# Controlador_repetidora.net
KiCad netlist of a schematic drawn in EAGLE
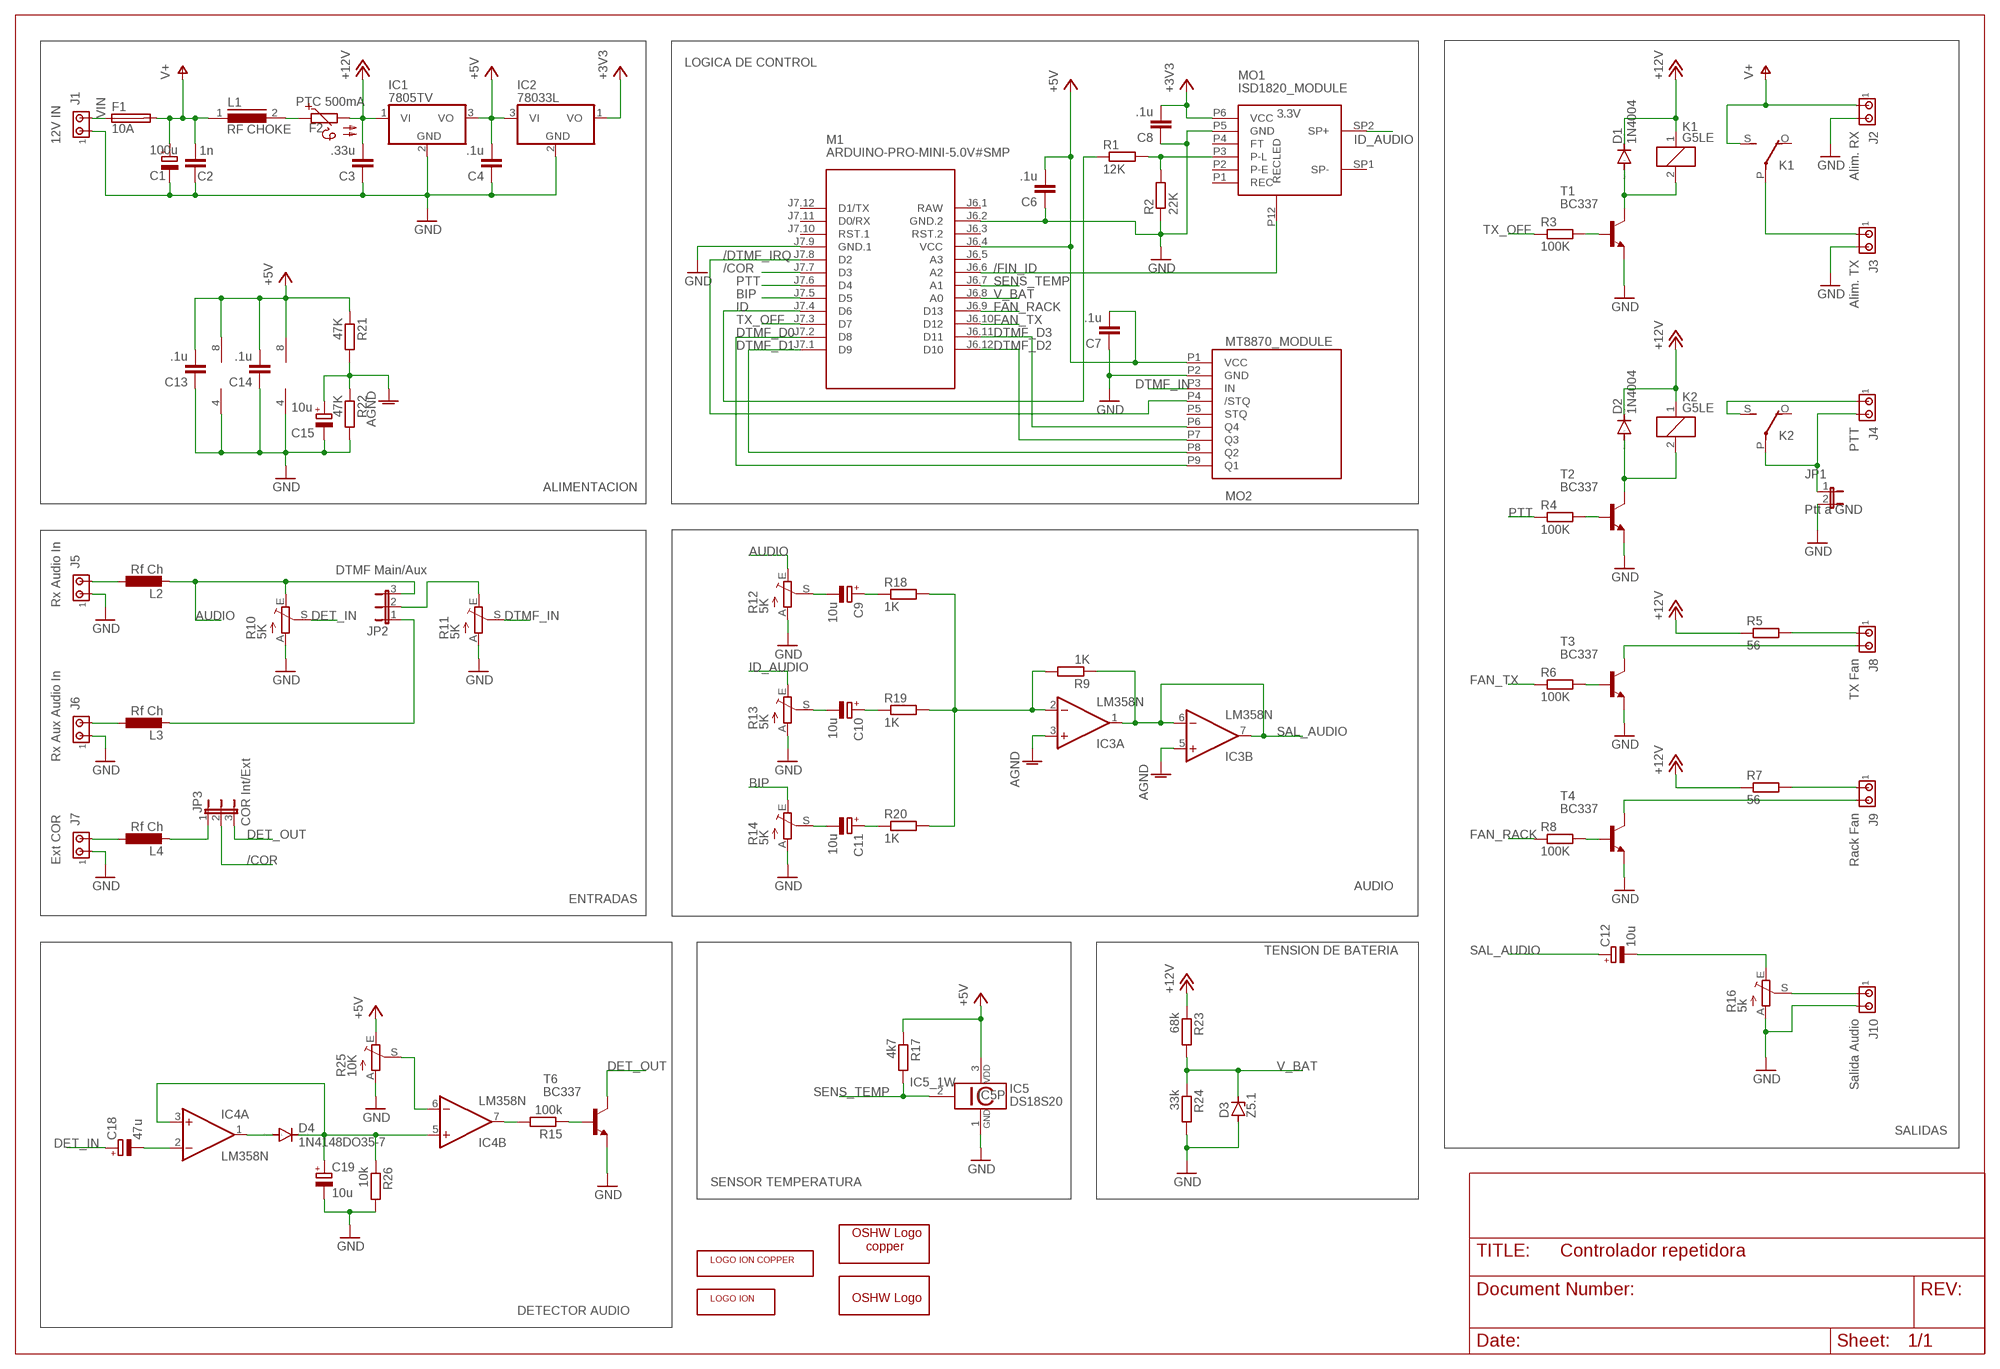
[diagram p0: schematic, sheet 1]

(export (version "E")
  (design (tool "Eeschema 10.0.6"))
  (components
    (comp (ref "C1")
      (value "100u")
      (footprint "eagle-import:E2,5-7")
      (libsource (lib "eagle-import") (part "CPOL-EUE2.5-7"))
    )
    (comp (ref "C2")
      (value "1n")
      (footprint "eagle-import:C025-025X050")
      (libsource (lib "eagle-import") (part "C-EU025-025X050"))
    )
    (comp (ref "C3")
      (value ".33u")
      (footprint "eagle-import:C025-025X050")
      (libsource (lib "eagle-import") (part "C-EU025-025X050"))
    )
    (comp (ref "C4")
      (value ".1u")
      (footprint "eagle-import:C025-025X050")
      (libsource (lib "eagle-import") (part "C-EU025-025X050"))
    )
    (comp (ref "C6")
      (value ".1u")
      (footprint "eagle-import:C025-025X050")
      (libsource (lib "eagle-import") (part "C-EU025-025X050"))
    )
    (comp (ref "C7")
      (value ".1u")
      (footprint "eagle-import:C025-025X050")
      (libsource (lib "eagle-import") (part "C-EU025-025X050"))
    )
    (comp (ref "C8")
      (value ".1u")
      (footprint "eagle-import:C025-025X050")
      (libsource (lib "eagle-import") (part "C-EU025-025X050"))
    )
    (comp (ref "C9")
      (value "10u")
      (footprint "eagle-import:E1,8-4")
      (libsource (lib "eagle-import") (part "CPOL-EUE1.8-4"))
    )
    (comp (ref "C10")
      (value "10u")
      (footprint "eagle-import:E1,8-4")
      (libsource (lib "eagle-import") (part "CPOL-EUE1.8-4"))
    )
    (comp (ref "C11")
      (value "10u")
      (footprint "eagle-import:E1,8-4")
      (libsource (lib "eagle-import") (part "CPOL-EUE1.8-4"))
    )
    (comp (ref "C12")
      (value "10u")
      (footprint "eagle-import:E1,8-4")
      (libsource (lib "eagle-import") (part "CPOL-EUE1.8-4"))
    )
    (comp (ref "C13")
      (value ".1u")
      (footprint "eagle-import:C025-025X050")
      (libsource (lib "eagle-import") (part "C-EU025-025X050"))
    )
    (comp (ref "C14")
      (value ".1u")
      (footprint "eagle-import:C025-025X050")
      (libsource (lib "eagle-import") (part "C-EU025-025X050"))
    )
    (comp (ref "C15")
      (value "10u")
      (footprint "eagle-import:E1,8-4")
      (libsource (lib "eagle-import") (part "CPOL-EUE1.8-4"))
    )
    (comp (ref "C18")
      (value "47u")
      (footprint "eagle-import:E1,8-4")
      (libsource (lib "eagle-import") (part "CPOL-EUE1.8-4"))
    )
    (comp (ref "C19")
      (value "10u")
      (footprint "eagle-import:E1,8-4")
      (libsource (lib "eagle-import") (part "CPOL-EUE1.8-4"))
    )
    (comp (ref "D1")
      (value "1N4004")
      (footprint "eagle-import:DO41-10")
      (libsource (lib "eagle-import") (part "1N4004"))
    )
    (comp (ref "D2")
      (value "1N4004")
      (footprint "eagle-import:DO41-10")
      (libsource (lib "eagle-import") (part "1N4004"))
    )
    (comp (ref "D3")
      (value "Z5.1")
      (footprint "eagle-import:DO34Z7")
      (libsource (lib "eagle-import") (part "ZENER-DIODEDO34-7"))
    )
    (comp (ref "D4")
      (value "1N4148DO35-7")
      (footprint "eagle-import:DO35-7")
      (libsource (lib "eagle-import") (part "1N4148DO35-7"))
    )
    (comp (ref "F1")
      (value "10A")
      (footprint "eagle-import:19559")
      (fields (field (name "MPN") "55900000001"))
      (libsource (lib "eagle-import") (part "19559"))
    )
    (comp (ref "F2")
      (value "PTC 500mA")
      (footprint "eagle-import:P660A")
      (libsource (lib "eagle-import") (part "PTC660A"))
    )
    (comp (ref "GOLD_ORB_SM1")
      (value "OSHWLOGOLOGO8MM")
      (footprint "eagle-import:OSHW_8MM")
      (libsource (lib "eagle-import") (part "OSHWLOGOLOGO8MM"))
    )
    (comp (ref "GOLD_ORB_SM2")
      (value "OSHWLOGO_COPPER8MM_COPPER")
      (footprint "eagle-import:OSHW_8MM_COPPER")
      (libsource (lib "eagle-import") (part "OSHWLOGO_COPPER8MM_COPPER"))
    )
    (comp (ref "IC1")
      (value "7805TV")
      (footprint "eagle-import:TO220V")
      (libsource (lib "eagle-import") (part "78TV05"))
    )
    (comp (ref "IC2")
      (value "78033L")
      (footprint "eagle-import:TO92")
      (libsource (lib "eagle-import") (part "78033L"))
    )
    (comp (ref "IC3")
      (value "LM358N")
      (footprint "eagle-import:DIL08")
      (libsource (lib "eagle-import") (part "LM358N"))
    )
    (comp (ref "IC4")
      (value "LM358N")
      (footprint "eagle-import:DIL08")
      (libsource (lib "eagle-import") (part "LM358N"))
    )
    (comp (ref "IC5")
      (value "DS18S20")
      (footprint "eagle-import:TO92-")
      (libsource (lib "eagle-import") (part "DS18S20"))
    )
    (comp (ref "J1")
      (value "12V IN")
      (footprint "eagle-import:1X2MTA")
      (libsource (lib "eagle-import") (part "MTA02-156"))
    )
    (comp (ref "J2")
      (value "Alim. RX")
      (footprint "eagle-import:1X2MTA")
      (libsource (lib "eagle-import") (part "MTA02-156"))
    )
    (comp (ref "J3")
      (value "Alim. TX")
      (footprint "eagle-import:1X2MTA")
      (libsource (lib "eagle-import") (part "MTA02-156"))
    )
    (comp (ref "J4")
      (value "PTT")
      (footprint "eagle-import:10X02MTA")
      (libsource (lib "eagle-import") (part "MTA02-100"))
    )
    (comp (ref "J5")
      (value "Rx Audio In")
      (footprint "eagle-import:10X02MTA")
      (libsource (lib "eagle-import") (part "MTA02-100"))
    )
    (comp (ref "J6")
      (value "Rx Aux Audio In")
      (footprint "eagle-import:10X02MTA")
      (libsource (lib "eagle-import") (part "MTA02-100"))
    )
    (comp (ref "J7")
      (value "Ext COR")
      (footprint "eagle-import:10X02MTA")
      (libsource (lib "eagle-import") (part "MTA02-100"))
    )
    (comp (ref "J8")
      (value "TX Fan")
      (footprint "eagle-import:10X02MTA")
      (libsource (lib "eagle-import") (part "MTA02-100"))
    )
    (comp (ref "J9")
      (value "Rack Fan")
      (footprint "eagle-import:10X02MTA")
      (libsource (lib "eagle-import") (part "MTA02-100"))
    )
    (comp (ref "J10")
      (value "Salida Audio")
      (footprint "eagle-import:10X02MTA")
      (libsource (lib "eagle-import") (part "MTA02-100"))
    )
    (comp (ref "JP1")
      (value "Ptt a GND")
      (footprint "eagle-import:JP1")
      (libsource (lib "eagle-import") (part "JP1E"))
    )
    (comp (ref "JP2")
      (value "DTMF Main/Aux")
      (footprint "eagle-import:JP2")
      (libsource (lib "eagle-import") (part "JP2E"))
    )
    (comp (ref "JP3")
      (value "COR Int/Ext")
      (footprint "eagle-import:JP2")
      (libsource (lib "eagle-import") (part "JP2E"))
    )
    (comp (ref "K1")
      (value "G5LE")
      (footprint "eagle-import:G5LE")
      (libsource (lib "eagle-import") (part "G5LE"))
    )
    (comp (ref "K2")
      (value "G5LE")
      (footprint "eagle-import:G5LE")
      (libsource (lib "eagle-import") (part "G5LE"))
    )
    (comp (ref "L1")
      (value "RF CHOKE")
      (footprint "eagle-import:82114A")
      (libsource (lib "eagle-import") (part "82114A"))
    )
    (comp (ref "L2")
      (value "Rf Ch")
      (footprint "eagle-import:0207_10")
      (libsource (lib "eagle-import") (part "L-EU0207/10"))
    )
    (comp (ref "L3")
      (value "Rf Ch")
      (footprint "eagle-import:0207_2V")
      (libsource (lib "eagle-import") (part "L-EU0207/2V"))
    )
    (comp (ref "L4")
      (value "Rf Ch")
      (footprint "eagle-import:0207_2V")
      (libsource (lib "eagle-import") (part "L-EU0207/2V"))
    )
    (comp (ref "M1")
      (value "ARDUINO-PRO-MINI-5.0V#SMP")
      (footprint "eagle-import:ARDUINO-PRO-MINI#SMP")
      (libsource (lib "eagle-import") (part "ARDUINO-PRO-MINI-#SMP5.0V"))
    )
    (comp (ref "MO1")
      (value "ISD1820_MODULE")
      (footprint "eagle-import:ISD1820_MODULE")
      (libsource (lib "eagle-import") (part "ISD1820_MODULE"))
    )
    (comp (ref "MO2")
      (value "MT8870_MODULE")
      (footprint "eagle-import:MT8870_MODULE")
      (libsource (lib "eagle-import") (part "MT8870_MODULE"))
    )
    (comp (ref "R1")
      (value "12K")
      (footprint "eagle-import:0207_12")
      (libsource (lib "eagle-import") (part "R-EU_0207/12"))
    )
    (comp (ref "R2")
      (value "22K")
      (footprint "eagle-import:0204_7")
      (libsource (lib "eagle-import") (part "R-EU_0204/7"))
    )
    (comp (ref "R3")
      (value "100K")
      (footprint "eagle-import:0207_10")
      (libsource (lib "eagle-import") (part "R-EU_0207/10"))
    )
    (comp (ref "R4")
      (value "100K")
      (footprint "eagle-import:0207_15")
      (libsource (lib "eagle-import") (part "R-EU_0207/15"))
    )
    (comp (ref "R5")
      (value "56")
      (footprint "eagle-import:0204_7")
      (libsource (lib "eagle-import") (part "R-EU_0204/7"))
    )
    (comp (ref "R6")
      (value "100K")
      (footprint "eagle-import:0207_2V")
      (libsource (lib "eagle-import") (part "R-EU_0207/2V"))
    )
    (comp (ref "R7")
      (value "56")
      (footprint "eagle-import:0204_7")
      (libsource (lib "eagle-import") (part "R-EU_0204/7"))
    )
    (comp (ref "R8")
      (value "100K")
      (footprint "eagle-import:0207_2V")
      (libsource (lib "eagle-import") (part "R-EU_0207/2V"))
    )
    (comp (ref "R9")
      (value "1K")
      (footprint "eagle-import:0204_7")
      (libsource (lib "eagle-import") (part "R-EU_0204/7"))
    )
    (comp (ref "R10")
      (value "5K")
      (footprint "eagle-import:CA6H")
      (libsource (lib "eagle-import") (part "TRIM_EU-CA6H"))
    )
    (comp (ref "R11")
      (value "5K")
      (footprint "eagle-import:CA6H")
      (libsource (lib "eagle-import") (part "TRIM_EU-CA6H"))
    )
    (comp (ref "R12")
      (value "5K")
      (footprint "eagle-import:CA6H")
      (libsource (lib "eagle-import") (part "TRIM_EU-CA6H"))
    )
    (comp (ref "R13")
      (value "5K")
      (footprint "eagle-import:CA6H")
      (libsource (lib "eagle-import") (part "TRIM_EU-CA6H"))
    )
    (comp (ref "R14")
      (value "5K")
      (footprint "eagle-import:CA6H")
      (libsource (lib "eagle-import") (part "TRIM_EU-CA6H"))
    )
    (comp (ref "R15")
      (value "100k")
      (footprint "eagle-import:0204_5")
      (libsource (lib "eagle-import") (part "R-EU_0204/5"))
    )
    (comp (ref "R16")
      (value "5k")
      (footprint "eagle-import:CA6H")
      (libsource (lib "eagle-import") (part "TRIM_EU-CA6H"))
    )
    (comp (ref "R17")
      (value "4k7")
      (footprint "eagle-import:0204_7")
      (libsource (lib "eagle-import") (part "R-EU_0204/7"))
    )
    (comp (ref "R18")
      (value "1K")
      (footprint "eagle-import:0204_7")
      (libsource (lib "eagle-import") (part "R-EU_0204/7"))
    )
    (comp (ref "R19")
      (value "1K")
      (footprint "eagle-import:0207_5V")
      (libsource (lib "eagle-import") (part "R-EU_0207/5V"))
    )
    (comp (ref "R20")
      (value "1K")
      (footprint "eagle-import:0204_7")
      (libsource (lib "eagle-import") (part "R-EU_0204/7"))
    )
    (comp (ref "R21")
      (value "47K")
      (footprint "eagle-import:0204_7")
      (libsource (lib "eagle-import") (part "R-EU_0204/7"))
    )
    (comp (ref "R22")
      (value "47K")
      (footprint "eagle-import:0207_2V")
      (libsource (lib "eagle-import") (part "R-EU_0207/2V"))
    )
    (comp (ref "R23")
      (value "68k")
      (footprint "eagle-import:0207_12")
      (libsource (lib "eagle-import") (part "R-EU_0207/12"))
    )
    (comp (ref "R24")
      (value "33k")
      (footprint "eagle-import:0204_7")
      (libsource (lib "eagle-import") (part "R-EU_0204/7"))
    )
    (comp (ref "R25")
      (value "10K")
      (footprint "eagle-import:CA6V")
      (libsource (lib "eagle-import") (part "TRIM_EU-CA6V"))
    )
    (comp (ref "R26")
      (value "10k")
      (footprint "eagle-import:0204_7")
      (libsource (lib "eagle-import") (part "R-EU_0204/7"))
    )
    (comp (ref "T1")
      (value "BC337")
      (footprint "eagle-import:TO92")
      (libsource (lib "eagle-import") (part "BC337"))
    )
    (comp (ref "T2")
      (value "BC337")
      (footprint "eagle-import:TO92")
      (libsource (lib "eagle-import") (part "BC337"))
    )
    (comp (ref "T3")
      (value "BC337")
      (footprint "eagle-import:TO92")
      (libsource (lib "eagle-import") (part "BC337"))
    )
    (comp (ref "T4")
      (value "BC337")
      (footprint "eagle-import:TO92")
      (libsource (lib "eagle-import") (part "BC337"))
    )
    (comp (ref "T6")
      (value "BC337")
      (footprint "eagle-import:TO92")
      (libsource (lib "eagle-import") (part "BC337"))
    )
    (comp (ref "U$1")
      (value "LOGO_ION")
      (footprint "eagle-import:LOGO_ION_SILK")
      (libsource (lib "eagle-import") (part "LOGO_ION"))
    )
    (comp (ref "U$2")
      (value "LOGO_ION_COOPER")
      (footprint "eagle-import:LOGO_ION_COPPER")
      (libsource (lib "eagle-import") (part "LOGO_ION_COOPER"))
    )
  )
  (nets
    (net (code "1") (name "+3V3") (class "Default")
      (node (ref "C8") (pin "2") (pinfunction "2_2") (pintype "passive"))
      (node (ref "IC2") (pin "1") (pinfunction "VO_1") (pintype "passive"))
      (node (ref "MO1") (pin "P6") (pinfunction "VCC_P6") (pintype "power_in"))
    )
    (net (code "2") (name "+5V") (class "Default")
      (node (ref "C13") (pin "2") (pinfunction "2_2") (pintype "passive"))
      (node (ref "C14") (pin "2") (pinfunction "2_2") (pintype "passive"))
      (node (ref "C4") (pin "2") (pinfunction "2_2") (pintype "passive"))
      (node (ref "C6") (pin "2") (pinfunction "2_2") (pintype "passive"))
      (node (ref "C7") (pin "2") (pinfunction "2_2") (pintype "passive"))
      (node (ref "IC1") (pin "3") (pinfunction "VO_3") (pintype "passive"))
      (node (ref "IC2") (pin "3") (pinfunction "VI_3") (pintype "input"))
      (node (ref "IC3") (pin "8") (pinfunction "V+_8") (pintype "power_in"))
      (node (ref "IC4") (pin "8") (pinfunction "V+_8") (pintype "power_in"))
      (node (ref "IC5") (pin "3") (pinfunction "VDD_3") (pintype "power_in"))
      (node (ref "M1") (pin "J6.4") (pinfunction "VCC_J6.4") (pintype "power_in"))
      (node (ref "MO2") (pin "P1") (pinfunction "VCC_P1") (pintype "power_in"))
      (node (ref "R17") (pin "1") (pinfunction "1_1") (pintype "passive"))
      (node (ref "R21") (pin "1") (pinfunction "1_1") (pintype "passive"))
      (node (ref "R25") (pin "E") (pinfunction "E_E") (pintype "passive"))
    )
    (net (code "3") (name "+12V") (class "Default")
      (node (ref "C3") (pin "2") (pinfunction "2_2") (pintype "passive"))
      (node (ref "D1") (pin "C") (pinfunction "C_C") (pintype "passive"))
      (node (ref "D2") (pin "C") (pinfunction "C_C") (pintype "passive"))
      (node (ref "F2") (pin "2") (pinfunction "2_2") (pintype "passive"))
      (node (ref "IC1") (pin "1") (pinfunction "VI_1") (pintype "input"))
      (node (ref "K1") (pin "1") (pinfunction "1_1") (pintype "passive"))
      (node (ref "K2") (pin "1") (pinfunction "1_1") (pintype "passive"))
      (node (ref "R23") (pin "1") (pinfunction "1_1") (pintype "passive"))
      (node (ref "R5") (pin "1") (pinfunction "1_1") (pintype "passive"))
      (node (ref "R7") (pin "1") (pinfunction "1_1") (pintype "passive"))
    )
    (net (code "4") (name "/AUDIO") (class "Default")
      (node (ref "JP2") (pin "3") (pinfunction "3_3") (pintype "passive"))
      (node (ref "L2") (pin "2") (pinfunction "2_2") (pintype "passive"))
      (node (ref "R10") (pin "E") (pinfunction "E_E") (pintype "passive"))
      (node (ref "R12") (pin "E") (pinfunction "E_E") (pintype "passive"))
    )
    (net (code "5") (name "/BIP") (class "Default")
      (node (ref "M1") (pin "J7.5") (pinfunction "D5_J7.5") (pintype "bidirectional"))
      (node (ref "R14") (pin "E") (pinfunction "E_E") (pintype "passive"))
    )
    (net (code "6") (name "/DET_IN") (class "Default")
      (node (ref "C18") (pin "+") (pinfunction "+_+") (pintype "passive"))
      (node (ref "R10") (pin "S") (pinfunction "S_S") (pintype "passive"))
    )
    (net (code "7") (name "/DET_OUT") (class "Default")
      (node (ref "JP3") (pin "3") (pinfunction "3_3") (pintype "passive"))
      (node (ref "T6") (pin "3") (pinfunction "C_3") (pintype "passive"))
    )
    (net (code "8") (name "/DTMF_D0") (class "Default")
      (node (ref "M1") (pin "J7.2") (pinfunction "D8_J7.2") (pintype "bidirectional"))
      (node (ref "MO2") (pin "P9") (pinfunction "Q1_P9") (pintype "output"))
    )
    (net (code "9") (name "/DTMF_D1") (class "Default")
      (node (ref "M1") (pin "J7.1") (pinfunction "D9_J7.1") (pintype "bidirectional"))
      (node (ref "MO2") (pin "P8") (pinfunction "Q2_P8") (pintype "output"))
    )
    (net (code "10") (name "/DTMF_D2") (class "Default")
      (node (ref "M1") (pin "J6.12") (pinfunction "D10_J6.12") (pintype "bidirectional"))
      (node (ref "MO2") (pin "P7") (pinfunction "Q3_P7") (pintype "output"))
    )
    (net (code "11") (name "/DTMF_D3") (class "Default")
      (node (ref "M1") (pin "J6.11") (pinfunction "D11_J6.11") (pintype "bidirectional"))
      (node (ref "MO2") (pin "P6") (pinfunction "Q4_P6") (pintype "output"))
    )
    (net (code "12") (name "/DTMF_IN") (class "Default")
      (node (ref "MO2") (pin "P3") (pinfunction "IN_P3") (pintype "input"))
      (node (ref "R11") (pin "S") (pinfunction "S_S") (pintype "passive"))
    )
    (net (code "13") (name "/FAN_RACK") (class "Default")
      (node (ref "M1") (pin "J6.9") (pinfunction "D13_J6.9") (pintype "bidirectional"))
      (node (ref "R8") (pin "1") (pinfunction "1_1") (pintype "passive"))
    )
    (net (code "14") (name "/FAN_TX") (class "Default")
      (node (ref "M1") (pin "J6.10") (pinfunction "D12_J6.10") (pintype "bidirectional"))
      (node (ref "R6") (pin "1") (pinfunction "1_1") (pintype "passive"))
    )
    (net (code "15") (name "/ID") (class "Default")
      (node (ref "M1") (pin "J7.4") (pinfunction "D6_J7.4") (pintype "bidirectional"))
      (node (ref "R1") (pin "1") (pinfunction "1_1") (pintype "passive"))
    )
    (net (code "16") (name "/ID_AUDIO") (class "Default")
      (node (ref "MO1") (pin "SP2") (pinfunction "SP+_SP2") (pintype "output"))
      (node (ref "R13") (pin "E") (pinfunction "E_E") (pintype "passive"))
    )
    (net (code "17") (name "/PTT") (class "Default")
      (node (ref "M1") (pin "J7.6") (pinfunction "D4_J7.6") (pintype "bidirectional"))
      (node (ref "R4") (pin "1") (pinfunction "1_1") (pintype "passive"))
    )
    (net (code "18") (name "/RAW") (class "Default")
      (node (ref "M1") (pin "J6.1") (pinfunction "RAW_J6.1") (pintype "power_in"))
    )
    (net (code "19") (name "/SAL_AUDIO") (class "Default")
      (node (ref "C12") (pin "+") (pinfunction "+_+") (pintype "passive"))
      (node (ref "IC3") (pin "1") (pinfunction "OUT_1") (pintype "output"))
      (node (ref "IC3") (pin "6") (pinfunction "-IN_6") (pintype "input"))
      (node (ref "IC3") (pin "7") (pinfunction "OUT_7") (pintype "output"))
      (node (ref "R9") (pin "1") (pinfunction "1_1") (pintype "passive"))
    )
    (net (code "20") (name "/SENS_TEMP") (class "Default")
      (node (ref "IC5") (pin "2") (pinfunction "1W_2") (pintype "power_in"))
      (node (ref "M1") (pin "J6.7") (pinfunction "A1_J6.7") (pintype "bidirectional"))
      (node (ref "R17") (pin "2") (pinfunction "2_2") (pintype "passive"))
    )
    (net (code "21") (name "/TX_OFF") (class "Default")
      (node (ref "M1") (pin "J7.3") (pinfunction "D7_J7.3") (pintype "bidirectional"))
      (node (ref "R3") (pin "1") (pinfunction "1_1") (pintype "passive"))
    )
    (net (code "22") (name "/VIN") (class "Default")
      (node (ref "F1") (pin "1") (pinfunction "1_1") (pintype "passive"))
      (node (ref "J1") (pin "2") (pinfunction "2_2") (pintype "passive"))
    )
    (net (code "23") (name "/V_BAT") (class "Default")
      (node (ref "D3") (pin "C") (pinfunction "C_C") (pintype "passive"))
      (node (ref "M1") (pin "J6.8") (pinfunction "A0_J6.8") (pintype "bidirectional"))
      (node (ref "R23") (pin "2") (pinfunction "2_2") (pintype "passive"))
      (node (ref "R24") (pin "1") (pinfunction "1_1") (pintype "passive"))
    )
    (net (code "24") (name "/{slash}COR") (class "Default")
      (node (ref "JP3") (pin "2") (pinfunction "2_2") (pintype "passive"))
      (node (ref "M1") (pin "J7.7") (pinfunction "D3_J7.7") (pintype "bidirectional"))
    )
    (net (code "25") (name "/{slash}DTMF_IRQ") (class "Default")
      (node (ref "M1") (pin "J7.8") (pinfunction "D2_J7.8") (pintype "bidirectional"))
      (node (ref "MO2") (pin "P4") (pinfunction "/STQ_P4") (pintype "output"))
    )
    (net (code "26") (name "/{slash}FIN_ID") (class "Default")
      (node (ref "M1") (pin "J6.6") (pinfunction "A2_J6.6") (pintype "bidirectional"))
      (node (ref "MO1") (pin "P12") (pinfunction "RECLED_P12") (pintype "output"))
    )
    (net (code "27") (name "AGND") (class "Default")
      (node (ref "C15") (pin "+") (pinfunction "+_+") (pintype "passive"))
      (node (ref "IC3") (pin "3") (pinfunction "+IN_3") (pintype "input"))
      (node (ref "IC3") (pin "5") (pinfunction "+IN_5") (pintype "input"))
      (node (ref "R21") (pin "2") (pinfunction "2_2") (pintype "passive"))
      (node (ref "R22") (pin "1") (pinfunction "1_1") (pintype "passive"))
    )
    (net (code "28") (name "GND") (class "Default")
      (node (ref "C1") (pin "-") (pinfunction "-_-") (pintype "passive"))
      (node (ref "C13") (pin "1") (pinfunction "1_1") (pintype "passive"))
      (node (ref "C14") (pin "1") (pinfunction "1_1") (pintype "passive"))
      (node (ref "C15") (pin "-") (pinfunction "-_-") (pintype "passive"))
      (node (ref "C19") (pin "-") (pinfunction "-_-") (pintype "passive"))
      (node (ref "C2") (pin "1") (pinfunction "1_1") (pintype "passive"))
      (node (ref "C3") (pin "1") (pinfunction "1_1") (pintype "passive"))
      (node (ref "C4") (pin "1") (pinfunction "1_1") (pintype "passive"))
      (node (ref "C6") (pin "1") (pinfunction "1_1") (pintype "passive"))
      (node (ref "C7") (pin "1") (pinfunction "1_1") (pintype "passive"))
      (node (ref "C8") (pin "1") (pinfunction "1_1") (pintype "passive"))
      (node (ref "D3") (pin "A") (pinfunction "A_A") (pintype "passive"))
      (node (ref "IC1") (pin "2") (pinfunction "GND_2") (pintype "passive"))
      (node (ref "IC2") (pin "2") (pinfunction "GND_2") (pintype "passive"))
      (node (ref "IC3") (pin "4") (pinfunction "V-_4") (pintype "power_in"))
      (node (ref "IC4") (pin "4") (pinfunction "V-_4") (pintype "power_in"))
      (node (ref "IC5") (pin "1") (pinfunction "GND_1") (pintype "power_in"))
      (node (ref "J1") (pin "1") (pinfunction "1_1") (pintype "passive"))
      (node (ref "J10") (pin "2") (pinfunction "2_2") (pintype "passive"))
      (node (ref "J2") (pin "2") (pinfunction "2_2") (pintype "passive"))
      (node (ref "J3") (pin "2") (pinfunction "2_2") (pintype "passive"))
      (node (ref "J5") (pin "1") (pinfunction "1_1") (pintype "passive"))
      (node (ref "J6") (pin "1") (pinfunction "1_1") (pintype "passive"))
      (node (ref "J7") (pin "1") (pinfunction "1_1") (pintype "passive"))
      (node (ref "JP1") (pin "2") (pinfunction "2_2") (pintype "passive"))
      (node (ref "M1") (pin "J6.2") (pinfunction "GND.2_J6.2") (pintype "power_in"))
      (node (ref "M1") (pin "J7.9") (pinfunction "GND.1_J7.9") (pintype "power_in"))
      (node (ref "MO1") (pin "P5") (pinfunction "GND_P5") (pintype "power_in"))
      (node (ref "MO2") (pin "P2") (pinfunction "GND_P2") (pintype "power_in"))
      (node (ref "R10") (pin "A") (pinfunction "A_A") (pintype "passive"))
      (node (ref "R11") (pin "A") (pinfunction "A_A") (pintype "passive"))
      (node (ref "R12") (pin "A") (pinfunction "A_A") (pintype "passive"))
      (node (ref "R13") (pin "A") (pinfunction "A_A") (pintype "passive"))
      (node (ref "R14") (pin "A") (pinfunction "A_A") (pintype "passive"))
      (node (ref "R16") (pin "A") (pinfunction "A_A") (pintype "passive"))
      (node (ref "R2") (pin "1") (pinfunction "1_1") (pintype "passive"))
      (node (ref "R22") (pin "2") (pinfunction "2_2") (pintype "passive"))
      (node (ref "R24") (pin "2") (pinfunction "2_2") (pintype "passive"))
      (node (ref "R25") (pin "A") (pinfunction "A_A") (pintype "passive"))
      (node (ref "R26") (pin "2") (pinfunction "2_2") (pintype "passive"))
      (node (ref "T1") (pin "1") (pinfunction "E_1") (pintype "passive"))
      (node (ref "T2") (pin "1") (pinfunction "E_1") (pintype "passive"))
      (node (ref "T3") (pin "1") (pinfunction "E_1") (pintype "passive"))
      (node (ref "T4") (pin "1") (pinfunction "E_1") (pintype "passive"))
      (node (ref "T6") (pin "1") (pinfunction "E_1") (pintype "passive"))
    )
    (net (code "29") (name "Net-(C9-Pad+)") (class "Default")
      (node (ref "C9") (pin "+") (pinfunction "+_+") (pintype "passive"))
      (node (ref "R18") (pin "1") (pinfunction "1_1") (pintype "passive"))
    )
    (net (code "30") (name "Net-(C9-Pad-)") (class "Default")
      (node (ref "C9") (pin "-") (pinfunction "-_-") (pintype "passive"))
      (node (ref "R12") (pin "S") (pinfunction "S_S") (pintype "passive"))
    )
    (net (code "31") (name "Net-(C10-Pad+)") (class "Default")
      (node (ref "C10") (pin "+") (pinfunction "+_+") (pintype "passive"))
      (node (ref "R19") (pin "1") (pinfunction "1_1") (pintype "passive"))
    )
    (net (code "32") (name "Net-(C10-Pad-)") (class "Default")
      (node (ref "C10") (pin "-") (pinfunction "-_-") (pintype "passive"))
      (node (ref "R13") (pin "S") (pinfunction "S_S") (pintype "passive"))
    )
    (net (code "33") (name "Net-(C11-Pad+)") (class "Default")
      (node (ref "C11") (pin "+") (pinfunction "+_+") (pintype "passive"))
      (node (ref "R20") (pin "1") (pinfunction "1_1") (pintype "passive"))
    )
    (net (code "34") (name "Net-(C11-Pad-)") (class "Default")
      (node (ref "C11") (pin "-") (pinfunction "-_-") (pintype "passive"))
      (node (ref "R14") (pin "S") (pinfunction "S_S") (pintype "passive"))
    )
    (net (code "35") (name "Net-(C12-Pad-)") (class "Default")
      (node (ref "C12") (pin "-") (pinfunction "-_-") (pintype "passive"))
      (node (ref "R16") (pin "E") (pinfunction "E_E") (pintype "passive"))
    )
    (net (code "36") (name "Net-(F2-Pad1)") (class "Default")
      (node (ref "F2") (pin "1") (pinfunction "1_1") (pintype "passive"))
      (node (ref "L1") (pin "2") (pinfunction "2_2") (pintype "passive"))
    )
    (net (code "37") (name "Net-(IC3A--IN)") (class "Default")
      (node (ref "IC3") (pin "2") (pinfunction "-IN_2") (pintype "input"))
      (node (ref "R18") (pin "2") (pinfunction "2_2") (pintype "passive"))
      (node (ref "R19") (pin "2") (pinfunction "2_2") (pintype "passive"))
      (node (ref "R20") (pin "2") (pinfunction "2_2") (pintype "passive"))
      (node (ref "R9") (pin "2") (pinfunction "2_2") (pintype "passive"))
    )
    (net (code "38") (name "Net-(IC4A-+IN)") (class "Default")
      (node (ref "C19") (pin "+") (pinfunction "+_+") (pintype "passive"))
      (node (ref "D4") (pin "C") (pinfunction "C_C") (pintype "passive"))
      (node (ref "IC4") (pin "3") (pinfunction "+IN_3") (pintype "input"))
      (node (ref "IC4") (pin "5") (pinfunction "+IN_5") (pintype "input"))
      (node (ref "R26") (pin "1") (pinfunction "1_1") (pintype "passive"))
    )
    (net (code "39") (name "Net-(IC4A--IN)") (class "Default")
      (node (ref "C18") (pin "-") (pinfunction "-_-") (pintype "passive"))
      (node (ref "IC4") (pin "2") (pinfunction "-IN_2") (pintype "input"))
    )
    (net (code "40") (name "Net-(IC4A-OUT)") (class "Default")
      (node (ref "D4") (pin "A") (pinfunction "A_A") (pintype "passive"))
      (node (ref "IC4") (pin "1") (pinfunction "OUT_1") (pintype "output"))
    )
    (net (code "41") (name "Net-(IC4B--IN)") (class "Default")
      (node (ref "IC4") (pin "6") (pinfunction "-IN_6") (pintype "input"))
      (node (ref "R25") (pin "S") (pinfunction "S_S") (pintype "passive"))
    )
    (net (code "42") (name "Net-(IC4B-OUT)") (class "Default")
      (node (ref "IC4") (pin "7") (pinfunction "OUT_7") (pintype "output"))
      (node (ref "R15") (pin "2") (pinfunction "2_2") (pintype "passive"))
    )
    (net (code "43") (name "Net-(J3-Pad1)") (class "Default")
      (node (ref "J3") (pin "1") (pinfunction "1_1") (pintype "passive"))
      (node (ref "K1") (pin "P") (pinfunction "P_P") (pintype "passive"))
    )
    (net (code "44") (name "Net-(J4-Pad1)") (class "Default")
      (node (ref "J4") (pin "1") (pinfunction "1_1") (pintype "passive"))
      (node (ref "K2") (pin "S") (pinfunction "S_S") (pintype "passive"))
    )
    (net (code "45") (name "Net-(J4-Pad2)") (class "Default")
      (node (ref "J4") (pin "2") (pinfunction "2_2") (pintype "passive"))
      (node (ref "JP1") (pin "1") (pinfunction "1_1") (pintype "passive"))
      (node (ref "K2") (pin "P") (pinfunction "P_P") (pintype "passive"))
    )
    (net (code "46") (name "Net-(J5-Pad2)") (class "Default")
      (node (ref "J5") (pin "2") (pinfunction "2_2") (pintype "passive"))
      (node (ref "L2") (pin "1") (pinfunction "1_1") (pintype "passive"))
    )
    (net (code "47") (name "Net-(J6-Pad2)") (class "Default")
      (node (ref "J6") (pin "2") (pinfunction "2_2") (pintype "passive"))
      (node (ref "L3") (pin "1") (pinfunction "1_1") (pintype "passive"))
    )
    (net (code "48") (name "Net-(J7-Pad2)") (class "Default")
      (node (ref "J7") (pin "2") (pinfunction "2_2") (pintype "passive"))
      (node (ref "L4") (pin "1") (pinfunction "1_1") (pintype "passive"))
    )
    (net (code "49") (name "Net-(J8-Pad1)") (class "Default")
      (node (ref "J8") (pin "1") (pinfunction "1_1") (pintype "passive"))
      (node (ref "R5") (pin "2") (pinfunction "2_2") (pintype "passive"))
    )
    (net (code "50") (name "Net-(J9-Pad1)") (class "Default")
      (node (ref "J9") (pin "1") (pinfunction "1_1") (pintype "passive"))
      (node (ref "R7") (pin "2") (pinfunction "2_2") (pintype "passive"))
    )
    (net (code "51") (name "Net-(J10-Pad1)") (class "Default")
      (node (ref "J10") (pin "1") (pinfunction "1_1") (pintype "passive"))
      (node (ref "R16") (pin "S") (pinfunction "S_S") (pintype "passive"))
    )
    (net (code "52") (name "Net-(JP2-Pad1)") (class "Default")
      (node (ref "JP2") (pin "1") (pinfunction "1_1") (pintype "passive"))
      (node (ref "L3") (pin "2") (pinfunction "2_2") (pintype "passive"))
    )
    (net (code "53") (name "Net-(JP2-Pad2)") (class "Default")
      (node (ref "JP2") (pin "2") (pinfunction "2_2") (pintype "passive"))
      (node (ref "R11") (pin "E") (pinfunction "E_E") (pintype "passive"))
    )
    (net (code "54") (name "Net-(JP3-Pad1)") (class "Default")
      (node (ref "JP3") (pin "1") (pinfunction "1_1") (pintype "passive"))
      (node (ref "L4") (pin "2") (pinfunction "2_2") (pintype "passive"))
    )
    (net (code "55") (name "Net-(MO1-P-L)") (class "Default")
      (node (ref "MO1") (pin "P3") (pinfunction "P-L_P3") (pintype "input"))
      (node (ref "R1") (pin "2") (pinfunction "2_2") (pintype "passive"))
      (node (ref "R2") (pin "2") (pinfunction "2_2") (pintype "passive"))
    )
    (net (code "56") (name "Net-(T1-B)") (class "Default")
      (node (ref "R3") (pin "2") (pinfunction "2_2") (pintype "passive"))
      (node (ref "T1") (pin "2") (pinfunction "B_2") (pintype "passive"))
    )
    (net (code "57") (name "Net-(T1-C)") (class "Default")
      (node (ref "D1") (pin "A") (pinfunction "A_A") (pintype "passive"))
      (node (ref "K1") (pin "2") (pinfunction "2_2") (pintype "passive"))
      (node (ref "T1") (pin "3") (pinfunction "C_3") (pintype "passive"))
    )
    (net (code "58") (name "Net-(T2-B)") (class "Default")
      (node (ref "R4") (pin "2") (pinfunction "2_2") (pintype "passive"))
      (node (ref "T2") (pin "2") (pinfunction "B_2") (pintype "passive"))
    )
    (net (code "59") (name "Net-(T2-C)") (class "Default")
      (node (ref "D2") (pin "A") (pinfunction "A_A") (pintype "passive"))
      (node (ref "K2") (pin "2") (pinfunction "2_2") (pintype "passive"))
      (node (ref "T2") (pin "3") (pinfunction "C_3") (pintype "passive"))
    )
    (net (code "60") (name "Net-(T3-B)") (class "Default")
      (node (ref "R6") (pin "2") (pinfunction "2_2") (pintype "passive"))
      (node (ref "T3") (pin "2") (pinfunction "B_2") (pintype "passive"))
    )
    (net (code "61") (name "Net-(T3-C)") (class "Default")
      (node (ref "J8") (pin "2") (pinfunction "2_2") (pintype "passive"))
      (node (ref "T3") (pin "3") (pinfunction "C_3") (pintype "passive"))
    )
    (net (code "62") (name "Net-(T4-B)") (class "Default")
      (node (ref "R8") (pin "2") (pinfunction "2_2") (pintype "passive"))
      (node (ref "T4") (pin "2") (pinfunction "B_2") (pintype "passive"))
    )
    (net (code "63") (name "Net-(T4-C)") (class "Default")
      (node (ref "J9") (pin "2") (pinfunction "2_2") (pintype "passive"))
      (node (ref "T4") (pin "3") (pinfunction "C_3") (pintype "passive"))
    )
    (net (code "64") (name "Net-(T6-B)") (class "Default")
      (node (ref "R15") (pin "1") (pinfunction "1_1") (pintype "passive"))
      (node (ref "T6") (pin "2") (pinfunction "B_2") (pintype "passive"))
    )
    (net (code "65") (name "V+") (class "Default")
      (node (ref "C1") (pin "+") (pinfunction "+_+") (pintype "passive"))
      (node (ref "C2") (pin "2") (pinfunction "2_2") (pintype "passive"))
      (node (ref "F1") (pin "2") (pinfunction "2_2") (pintype "passive"))
      (node (ref "J2") (pin "1") (pinfunction "1_1") (pintype "passive"))
      (node (ref "K1") (pin "S") (pinfunction "S_S") (pintype "passive"))
      (node (ref "L1") (pin "1") (pinfunction "1_1") (pintype "passive"))
    )
    (net (code "66") (name "unconnected-(K1-PadO)") (class "Default")
      (node (ref "K1") (pin "O") (pinfunction "O_O") (pintype "passive"))
    )
    (net (code "67") (name "unconnected-(K2-PadO)") (class "Default")
      (node (ref "K2") (pin "O") (pinfunction "O_O") (pintype "passive"))
    )
    (net (code "68") (name "unconnected-(M1-A3-PadJ6.5)") (class "Default")
      (node (ref "M1") (pin "J6.5") (pinfunction "A3_J6.5") (pintype "bidirectional"))
    )
    (net (code "69") (name "unconnected-(M1-D0{slash}RX-PadJ7.11)") (class "Default")
      (node (ref "M1") (pin "J7.11") (pinfunction "D0/RX_J7.11") (pintype "bidirectional"))
    )
    (net (code "70") (name "unconnected-(M1-D1{slash}TX-PadJ7.12)") (class "Default")
      (node (ref "M1") (pin "J7.12") (pinfunction "D1/TX_J7.12") (pintype "bidirectional"))
    )
    (net (code "71") (name "unconnected-(M1-RST.1-PadJ7.10)") (class "Default")
      (node (ref "M1") (pin "J7.10") (pinfunction "RST.1_J7.10") (pintype "bidirectional"))
    )
    (net (code "72") (name "unconnected-(M1-RST.2-PadJ6.3)") (class "Default")
      (node (ref "M1") (pin "J6.3") (pinfunction "RST.2_J6.3") (pintype "bidirectional"))
    )
    (net (code "73") (name "unconnected-(MO1-FT-PadP4)") (class "Default")
      (node (ref "MO1") (pin "P4") (pinfunction "FT_P4") (pintype "input"))
    )
    (net (code "74") (name "unconnected-(MO1-P-E-PadP2)") (class "Default")
      (node (ref "MO1") (pin "P2") (pinfunction "P-E_P2") (pintype "input"))
    )
    (net (code "75") (name "unconnected-(MO1-REC-PadP1)") (class "Default")
      (node (ref "MO1") (pin "P1") (pinfunction "REC_P1") (pintype "input"))
    )
    (net (code "76") (name "unconnected-(MO1-SP--PadSP1)") (class "Default")
      (node (ref "MO1") (pin "SP1") (pinfunction "SP-_SP1") (pintype "output"))
    )
    (net (code "77") (name "unconnected-(MO2-STQ-PadP5)") (class "Default")
      (node (ref "MO2") (pin "P5") (pinfunction "STQ_P5") (pintype "output"))
    )
  )
)
